# 2.net
KiCad netlist of a schematic drawn in Altium Designer
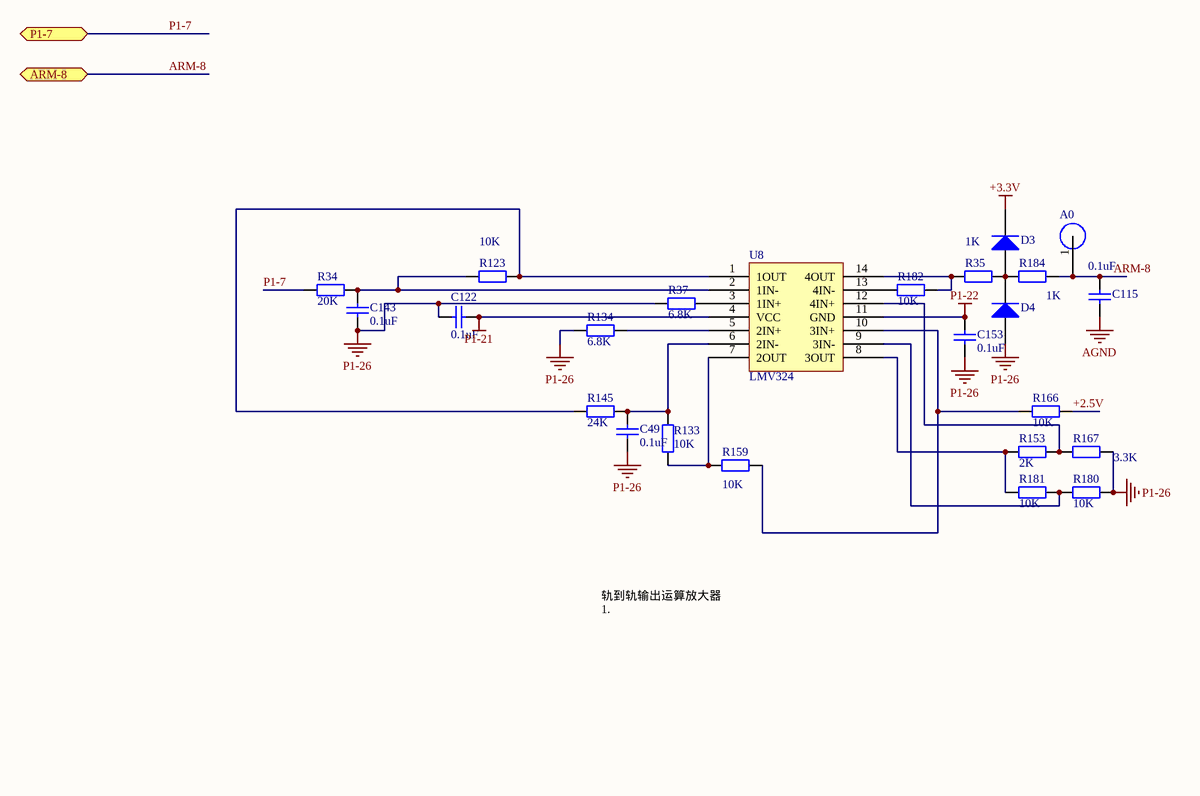
[diagram p0: 四通道输出运算放大（2）.SchDoc]

(export (version "E")
  (design (tool "Eeschema 10.0.6"))
  (components
    (comp (ref "A0") (value "PIN") (footprint "圆形焊盘") (libsource (lib "圆孔") (part "Component_1")))
    (comp (ref "C49")
      (value "0.1uF")
      (footprint "采集板3.0增加1路模拟量2:C0805")
      (description "Capacitor")
      (fields (field (name "Comment") "Cap") (field (name "PUBLISHER") "Altium Limited"))
      (libsource (lib "Miscellaneous Devices") (part "Cap"))
    )
    (comp (ref "C115")
      (value "0.1uF")
      (footprint "采集板3.0增加1路模拟量2:C0805")
      (description "Capacitor")
      (fields (field (name "Comment") "Cap") (field (name "PUBLISHER") "Altium Limited"))
      (libsource (lib "Miscellaneous Devices") (part "Cap"))
    )
    (comp (ref "C122")
      (value "0.1uF")
      (footprint "采集板3.0增加1路模拟量2:C0805")
      (description "Capacitor")
      (fields (field (name "Comment") "Cap") (field (name "PUBLISHER") "Altium Limited"))
      (libsource (lib "Miscellaneous Devices") (part "Cap"))
    )
    (comp (ref "C143")
      (value "0.1uF")
      (footprint "采集板3.0增加1路模拟量2:C0805")
      (description "Capacitor")
      (fields (field (name "Comment") "Cap") (field (name "PUBLISHER") "Altium Limited"))
      (libsource (lib "Miscellaneous Devices") (part "Cap"))
    )
    (comp (ref "C153")
      (value "0.1uF")
      (footprint "采集板3.0增加1路模拟量2:C0805")
      (description "Capacitor")
      (fields (field (name "Comment") "Cap") (field (name "PUBLISHER") "Altium Limited"))
      (libsource (lib "Miscellaneous Devices") (part "Cap"))
    )
    (comp (ref "D3")
      (value "Diode 1N4007")
      (footprint "SOD123")
      (description "1 Amp General Purpose Rectifier")
      (fields (field (name "PUBLISHER") "Altium Limited"))
      (libsource (lib "Miscellaneous Devices") (part "Diode 1N4007"))
    )
    (comp (ref "D4")
      (value "Diode 1N4007")
      (footprint "SOD123")
      (description "1 Amp General Purpose Rectifier")
      (fields (field (name "PUBLISHER") "Altium Limited"))
      (libsource (lib "Miscellaneous Devices") (part "Diode 1N4007"))
    )
    (comp (ref "R34")
      (value "20K")
      (footprint "采集板3.0增加1路模拟量2:R0805")
      (description "Resistor")
      (fields (field (name "Comment") "Res2") (field (name "PUBLISHER") "Altium Limited"))
      (libsource (lib "Miscellaneous Devices") (part "Res2"))
    )
    (comp (ref "R35")
      (value "1K")
      (footprint "采集板3.0增加1路模拟量2:R0805")
      (description "Resistor")
      (fields (field (name "Comment") "Res2") (field (name "PUBLISHER") "Altium Limited"))
      (libsource (lib "Miscellaneous Devices") (part "Res2"))
    )
    (comp (ref "R37")
      (value "6.8K")
      (footprint "采集板3.0增加1路模拟量2:R0805")
      (description "Resistor")
      (fields (field (name "Comment") "Res2") (field (name "PUBLISHER") "Altium Limited"))
      (libsource (lib "Miscellaneous Devices") (part "Res2"))
    )
    (comp (ref "R123")
      (value "10K")
      (footprint "采集板3.0增加1路模拟量2:R0805")
      (description "Resistor")
      (fields (field (name "Comment") "Res2") (field (name "PUBLISHER") "Altium Limited"))
      (libsource (lib "") (part "Res2_1"))
    )
    (comp (ref "R133")
      (value "10K")
      (footprint "采集板3.0增加1路模拟量2:R0805")
      (description "Resistor")
      (fields (field (name "Comment") "Res2") (field (name "PUBLISHER") "Altium Limited"))
      (libsource (lib "") (part "Res2_2"))
    )
    (comp (ref "R134")
      (value "6.8K")
      (footprint "采集板3.0增加1路模拟量2:R0805")
      (description "Resistor")
      (fields (field (name "Comment") "Res2") (field (name "PUBLISHER") "Altium Limited"))
      (libsource (lib "Miscellaneous Devices") (part "Res2"))
    )
    (comp (ref "R145")
      (value "24K")
      (footprint "采集板3.0增加1路模拟量2:R0805")
      (description "Resistor")
      (fields (field (name "Comment") "Res2") (field (name "PUBLISHER") "Altium Limited"))
      (libsource (lib "Miscellaneous Devices") (part "Res2"))
    )
    (comp (ref "R153")
      (value "2K")
      (footprint "采集板3.0增加1路模拟量2:R0805")
      (description "Resistor")
      (fields (field (name "Comment") "Res2") (field (name "PUBLISHER") "Altium Limited"))
      (libsource (lib "") (part "Res2_1"))
    )
    (comp (ref "R159")
      (value "10K")
      (footprint "采集板3.0增加1路模拟量2:R0805")
      (description "Resistor")
      (fields (field (name "Comment") "Res2") (field (name "PUBLISHER") "Altium Limited"))
      (libsource (lib "Miscellaneous Devices") (part "Res2"))
    )
    (comp (ref "R166")
      (value "10K")
      (footprint "采集板3.0增加1路模拟量2:R0805")
      (description "Resistor")
      (fields (field (name "Comment") "Res2") (field (name "PUBLISHER") "Altium Limited"))
      (libsource (lib "") (part "Res2_1"))
    )
    (comp (ref "R167")
      (value "3.3K")
      (footprint "采集板3.0增加1路模拟量2:R0805")
      (description "Resistor")
      (fields (field (name "Comment") "Res2") (field (name "PUBLISHER") "Altium Limited"))
      (libsource (lib "Miscellaneous Devices") (part "Res2"))
    )
    (comp (ref "R180")
      (value "10K")
      (footprint "采集板3.0增加1路模拟量2:R0805")
      (description "Resistor")
      (fields (field (name "Comment") "Res2") (field (name "PUBLISHER") "Altium Limited"))
      (libsource (lib "") (part "Res2_1"))
    )
    (comp (ref "R181")
      (value "10K")
      (footprint "采集板3.0增加1路模拟量2:R0805")
      (description "Resistor")
      (fields (field (name "Comment") "Res2") (field (name "PUBLISHER") "Altium Limited"))
      (libsource (lib "") (part "Res2_1"))
    )
    (comp (ref "R182")
      (value "10K")
      (footprint "采集板3.0增加1路模拟量2:R0805")
      (description "Resistor")
      (fields (field (name "Comment") "Res2") (field (name "PUBLISHER") "Altium Limited"))
      (libsource (lib "") (part "Res2_1"))
    )
    (comp (ref "R184")
      (value "1K")
      (footprint "采集板3.0增加1路模拟量2:R0805")
      (description "Resistor")
      (fields (field (name "Comment") "Res2") (field (name "PUBLISHER") "Altium Limited"))
      (libsource (lib "Miscellaneous Devices") (part "Res2"))
    )
    (comp (ref "U8") (value "LMV324") (footprint "SOP-14") (libsource (lib "LMV324") (part "Component_1")))
  )
  (nets
    (net (code "1") (name "+3.3V") (class "Default")
      (node (ref "D3") (pin "2") (pinfunction "K_2") (pintype "passive"))
    )
    (net (code "2") (name "/+2.5V") (class "Default")
      (node (ref "R166") (pin "1") (pinfunction "1_1") (pintype "passive"))
    )
    (net (code "3") (name "/ARM-8") (class "Default")
      (node (ref "A0") (pin "1") (pinfunction "1_1") (pintype "passive"))
      (node (ref "C115") (pin "2") (pinfunction "2_2") (pintype "passive"))
      (node (ref "R184") (pin "2") (pinfunction "2_2") (pintype "passive"))
    )
    (net (code "4") (name "/P1-7") (class "Default")
      (node (ref "R34") (pin "1") (pinfunction "1_1") (pintype "passive"))
    )
    (net (code "5") (name "AGND") (class "Default")
      (node (ref "C115") (pin "1") (pinfunction "1_1") (pintype "passive"))
    )
    (net (code "6") (name "Net-(D3-A)") (class "Default")
      (node (ref "D3") (pin "1") (pinfunction "A_1") (pintype "passive"))
      (node (ref "D4") (pin "2") (pinfunction "K_2") (pintype "passive"))
      (node (ref "R184") (pin "1") (pinfunction "1_1") (pintype "passive"))
      (node (ref "R35") (pin "2") (pinfunction "2_2") (pintype "passive"))
    )
    (net (code "7") (name "Net-(U8-1IN+)") (class "Default")
      (node (ref "R37") (pin "2") (pinfunction "2_2") (pintype "passive"))
      (node (ref "U8") (pin "3") (pinfunction "1IN+_3") (pintype "passive"))
    )
    (net (code "8") (name "Net-(U8-1IN-)") (class "Default")
      (node (ref "C143") (pin "1") (pinfunction "1_1") (pintype "passive"))
      (node (ref "R123") (pin "2") (pinfunction "2_2") (pintype "passive"))
      (node (ref "R34") (pin "2") (pinfunction "2_2") (pintype "passive"))
      (node (ref "U8") (pin "2") (pinfunction "1IN-_2") (pintype "passive"))
    )
    (net (code "9") (name "Net-(U8-1OUT)") (class "Default")
      (node (ref "R123") (pin "1") (pinfunction "1_1") (pintype "passive"))
      (node (ref "R145") (pin "1") (pinfunction "1_1") (pintype "passive"))
      (node (ref "U8") (pin "1") (pinfunction "1OUT_1") (pintype "passive"))
    )
    (net (code "10") (name "Net-(U8-2IN+)") (class "Default")
      (node (ref "R134") (pin "2") (pinfunction "2_2") (pintype "passive"))
      (node (ref "U8") (pin "5") (pinfunction "2IN+_5") (pintype "passive"))
    )
    (net (code "11") (name "Net-(U8-2IN-)") (class "Default")
      (node (ref "C49") (pin "1") (pinfunction "1_1") (pintype "passive"))
      (node (ref "R133") (pin "2") (pinfunction "2_2") (pintype "passive"))
      (node (ref "R145") (pin "2") (pinfunction "2_2") (pintype "passive"))
      (node (ref "U8") (pin "6") (pinfunction "2IN-_6") (pintype "passive"))
    )
    (net (code "12") (name "Net-(U8-2OUT)") (class "Default")
      (node (ref "R133") (pin "1") (pinfunction "1_1") (pintype "passive"))
      (node (ref "R159") (pin "1") (pinfunction "1_1") (pintype "passive"))
      (node (ref "U8") (pin "7") (pinfunction "2OUT_7") (pintype "passive"))
    )
    (net (code "13") (name "Net-(U8-3IN+)") (class "Default")
      (node (ref "R159") (pin "2") (pinfunction "2_2") (pintype "passive"))
      (node (ref "R166") (pin "2") (pinfunction "2_2") (pintype "passive"))
      (node (ref "U8") (pin "10") (pinfunction "3IN+_10") (pintype "passive"))
    )
    (net (code "14") (name "Net-(U8-3IN-)") (class "Default")
      (node (ref "R180") (pin "2") (pinfunction "2_2") (pintype "passive"))
      (node (ref "R181") (pin "1") (pinfunction "1_1") (pintype "passive"))
      (node (ref "U8") (pin "9") (pinfunction "3IN-_9") (pintype "passive"))
    )
    (net (code "15") (name "Net-(U8-3OUT)") (class "Default")
      (node (ref "R153") (pin "2") (pinfunction "2_2") (pintype "passive"))
      (node (ref "R181") (pin "2") (pinfunction "2_2") (pintype "passive"))
      (node (ref "U8") (pin "8") (pinfunction "3OUT_8") (pintype "passive"))
    )
    (net (code "16") (name "Net-(U8-4IN+)") (class "Default")
      (node (ref "R153") (pin "1") (pinfunction "1_1") (pintype "passive"))
      (node (ref "R167") (pin "1") (pinfunction "1_1") (pintype "passive"))
      (node (ref "U8") (pin "12") (pinfunction "4IN+_12") (pintype "passive"))
    )
    (net (code "17") (name "Net-(U8-4IN-)") (class "Default")
      (node (ref "R182") (pin "2") (pinfunction "2_2") (pintype "passive"))
      (node (ref "U8") (pin "13") (pinfunction "4IN-_13") (pintype "passive"))
    )
    (net (code "18") (name "Net-(U8-4OUT)") (class "Default")
      (node (ref "R182") (pin "1") (pinfunction "1_1") (pintype "passive"))
      (node (ref "R35") (pin "1") (pinfunction "1_1") (pintype "passive"))
      (node (ref "U8") (pin "14") (pinfunction "4OUT_14") (pintype "passive"))
    )
    (net (code "19") (name "P1-21") (class "Default")
      (node (ref "C122") (pin "2") (pinfunction "2_2") (pintype "passive"))
      (node (ref "U8") (pin "4") (pinfunction "VCC_4") (pintype "passive"))
    )
    (net (code "20") (name "P1-22") (class "Default")
      (node (ref "C153") (pin "1") (pinfunction "1_1") (pintype "passive"))
      (node (ref "U8") (pin "11") (pinfunction "GND_11") (pintype "passive"))
    )
    (net (code "21") (name "P1-26") (class "Default")
      (node (ref "C122") (pin "1") (pinfunction "1_1") (pintype "passive"))
      (node (ref "C143") (pin "2") (pinfunction "2_2") (pintype "passive"))
      (node (ref "C153") (pin "2") (pinfunction "2_2") (pintype "passive"))
      (node (ref "C49") (pin "2") (pinfunction "2_2") (pintype "passive"))
      (node (ref "D4") (pin "1") (pinfunction "A_1") (pintype "passive"))
      (node (ref "R134") (pin "1") (pinfunction "1_1") (pintype "passive"))
      (node (ref "R167") (pin "2") (pinfunction "2_2") (pintype "passive"))
      (node (ref "R180") (pin "1") (pinfunction "1_1") (pintype "passive"))
      (node (ref "R37") (pin "1") (pinfunction "1_1") (pintype "passive"))
    )
  )
)
